# 04_LED.net
KiCad netlist of a schematic drawn in Altium Designer
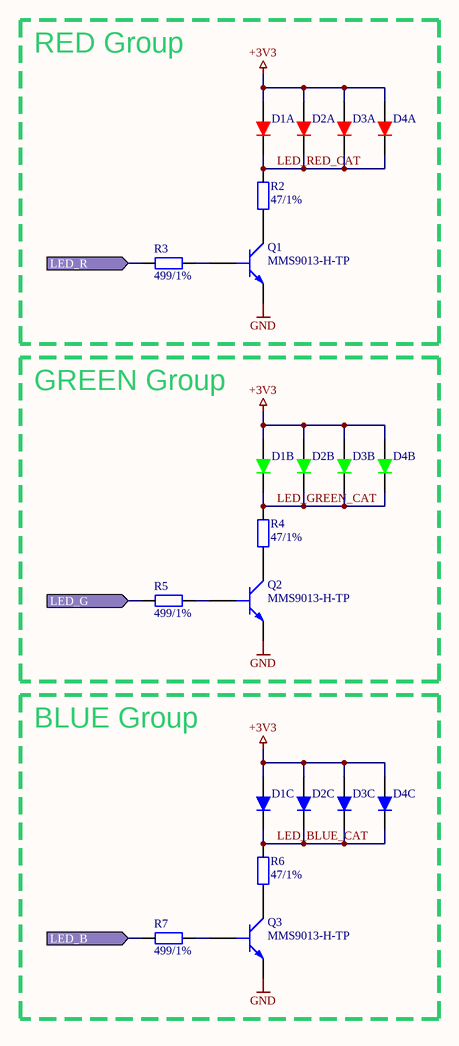
[diagram p0: 04 LED.SchDoc]

(export (version "E")
  (design (tool "Eeschema 10.0.6"))
  (components
    (comp (ref "D1")
      (value "NH-B2020RGBA-HF")
      (footprint "NH-B2020RGBA-HF")
      (description "-30℃~+85℃ Common anode RGB 110° SMD,2.1x2.1mm  Light Emitting Diodes (LED) ROHS")
      (fields (field (name "MANUFACTURER") "Foshan NationStar Optoelectronics"))
      (libsource (lib "altium_symbol") (part "NH-B2020RGBA-HF"))
    )
    (comp (ref "D2")
      (value "NH-B2020RGBA-HF")
      (footprint "NH-B2020RGBA-HF")
      (description "-30℃~+85℃ Common anode RGB 110° SMD,2.1x2.1mm  Light Emitting Diodes (LED) ROHS")
      (fields (field (name "MANUFACTURER") "Foshan NationStar Optoelectronics"))
      (libsource (lib "altium_symbol") (part "NH-B2020RGBA-HF"))
    )
    (comp (ref "D3")
      (value "NH-B2020RGBA-HF")
      (footprint "NH-B2020RGBA-HF")
      (description "-30℃~+85℃ Common anode RGB 110° SMD,2.1x2.1mm  Light Emitting Diodes (LED) ROHS")
      (fields (field (name "MANUFACTURER") "Foshan NationStar Optoelectronics"))
      (libsource (lib "altium_symbol") (part "NH-B2020RGBA-HF"))
    )
    (comp (ref "D4")
      (value "NH-B2020RGBA-HF")
      (footprint "NH-B2020RGBA-HF")
      (description "-30℃~+85℃ Common anode RGB 110° SMD,2.1x2.1mm  Light Emitting Diodes (LED) ROHS")
      (fields (field (name "MANUFACTURER") "Foshan NationStar Optoelectronics"))
      (libsource (lib "altium_symbol") (part "NH-B2020RGBA-HF"))
    )
    (comp (ref "Q1")
      (value "MMS9013-H-TP")
      (footprint "SOT95P237X110-3N")
      (fields (field (name "MANUFACTURER") "MCC(Micro Commercial Components)"))
      (libsource (lib "altium_symbol") (part "MMS9013-H-TP"))
    )
    (comp (ref "Q2")
      (value "MMS9013-H-TP")
      (footprint "SOT95P237X110-3N")
      (fields (field (name "MANUFACTURER") "MCC(Micro Commercial Components)"))
      (libsource (lib "altium_symbol") (part "MMS9013-H-TP"))
    )
    (comp (ref "Q3")
      (value "MMS9013-H-TP")
      (footprint "SOT95P237X110-3N")
      (fields (field (name "MANUFACTURER") "MCC(Micro Commercial Components)"))
      (libsource (lib "altium_symbol") (part "MMS9013-H-TP"))
    )
    (comp (ref "R2")
      (value "47/1%")
      (footprint "RESC1005X04N")
      (description "62.5mW ±5% 47Ω 0402  Chip Resistor - Surface Mount ROHS")
      (fields
        (field (name "MANUFACTURER") "HKR(Hong Kong Resistors)")
        (field (name "MFR_PART_NUMBER") "RCT0247RJLF")
      )
      (libsource (lib "altium_symbol") (part "RCT0247RJLF"))
    )
    (comp (ref "R3")
      (value "499/1%")
      (footprint "RESC1005X04N")
      (fields (field (name "MANUFACTURER") "YAGEO") (field (name "MFR_PART_NUMBER") "RC0402FR-07499RL"))
      (libsource (lib "altium_symbol") (part "RC0402FR-07499RL"))
    )
    (comp (ref "R4")
      (value "47/1%")
      (footprint "RESC1005X04N")
      (description "62.5mW ±5% 47Ω 0402  Chip Resistor - Surface Mount ROHS")
      (fields
        (field (name "MANUFACTURER") "HKR(Hong Kong Resistors)")
        (field (name "MFR_PART_NUMBER") "RCT0247RJLF")
      )
      (libsource (lib "altium_symbol") (part "RCT0247RJLF"))
    )
    (comp (ref "R5")
      (value "499/1%")
      (footprint "RESC1005X04N")
      (fields (field (name "MANUFACTURER") "YAGEO") (field (name "MFR_PART_NUMBER") "RC0402FR-07499RL"))
      (libsource (lib "altium_symbol") (part "RC0402FR-07499RL"))
    )
    (comp (ref "R6")
      (value "47/1%")
      (footprint "RESC1005X04N")
      (description "62.5mW ±5% 47Ω 0402  Chip Resistor - Surface Mount ROHS")
      (fields
        (field (name "MANUFACTURER") "HKR(Hong Kong Resistors)")
        (field (name "MFR_PART_NUMBER") "RCT0247RJLF")
      )
      (libsource (lib "altium_symbol") (part "RCT0247RJLF"))
    )
    (comp (ref "R7")
      (value "499/1%")
      (footprint "RESC1005X04N")
      (fields (field (name "MANUFACTURER") "YAGEO") (field (name "MFR_PART_NUMBER") "RC0402FR-07499RL"))
      (libsource (lib "altium_symbol") (part "RC0402FR-07499RL"))
    )
  )
  (nets
    (net (code "1") (name "+3V3") (class "Default")
      (node (ref "D1") (pin "3") (pinfunction "3_3") (pintype "passive"))
      (node (ref "D2") (pin "3") (pinfunction "3_3") (pintype "passive"))
      (node (ref "D3") (pin "3") (pinfunction "3_3") (pintype "passive"))
      (node (ref "D4") (pin "3") (pinfunction "3_3") (pintype "passive"))
    )
    (net (code "2") (name "/LED_B") (class "Default")
      (node (ref "R7") (pin "2") (pinfunction "2_2") (pintype "passive"))
    )
    (net (code "3") (name "/LED_BLUE_CAT") (class "Default")
      (node (ref "D1") (pin "2") (pinfunction "2_2") (pintype "passive"))
      (node (ref "D2") (pin "2") (pinfunction "2_2") (pintype "passive"))
      (node (ref "D3") (pin "2") (pinfunction "2_2") (pintype "passive"))
      (node (ref "D4") (pin "2") (pinfunction "2_2") (pintype "passive"))
      (node (ref "R6") (pin "2") (pinfunction "2_2") (pintype "passive"))
    )
    (net (code "4") (name "/LED_G") (class "Default")
      (node (ref "R5") (pin "2") (pinfunction "2_2") (pintype "passive"))
    )
    (net (code "5") (name "/LED_GREEN_CAT") (class "Default")
      (node (ref "D1") (pin "4") (pinfunction "4_4") (pintype "passive"))
      (node (ref "D2") (pin "4") (pinfunction "4_4") (pintype "passive"))
      (node (ref "D3") (pin "4") (pinfunction "4_4") (pintype "passive"))
      (node (ref "D4") (pin "4") (pinfunction "4_4") (pintype "passive"))
      (node (ref "R4") (pin "2") (pinfunction "2_2") (pintype "passive"))
    )
    (net (code "6") (name "/LED_R") (class "Default")
      (node (ref "R3") (pin "2") (pinfunction "2_2") (pintype "passive"))
    )
    (net (code "7") (name "/LED_RED_CAT") (class "Default")
      (node (ref "D1") (pin "1") (pinfunction "1_1") (pintype "passive"))
      (node (ref "D2") (pin "1") (pinfunction "1_1") (pintype "passive"))
      (node (ref "D3") (pin "1") (pinfunction "1_1") (pintype "passive"))
      (node (ref "D4") (pin "1") (pinfunction "1_1") (pintype "passive"))
      (node (ref "R2") (pin "2") (pinfunction "2_2") (pintype "passive"))
    )
    (net (code "8") (name "GND") (class "Default")
      (node (ref "Q1") (pin "2") (pinfunction "2_2") (pintype "passive"))
      (node (ref "Q2") (pin "2") (pinfunction "2_2") (pintype "passive"))
      (node (ref "Q3") (pin "2") (pinfunction "2_2") (pintype "passive"))
    )
    (net (code "9") (name "Net-(Q1-Pad1)") (class "Default")
      (node (ref "Q1") (pin "1") (pinfunction "1_1") (pintype "passive"))
      (node (ref "R3") (pin "1") (pinfunction "1_1") (pintype "passive"))
    )
    (net (code "10") (name "Net-(Q1-Pad3)") (class "Default")
      (node (ref "Q1") (pin "3") (pinfunction "3_3") (pintype "passive"))
      (node (ref "R2") (pin "1") (pinfunction "1_1") (pintype "passive"))
    )
    (net (code "11") (name "Net-(Q2-Pad1)") (class "Default")
      (node (ref "Q2") (pin "1") (pinfunction "1_1") (pintype "passive"))
      (node (ref "R5") (pin "1") (pinfunction "1_1") (pintype "passive"))
    )
    (net (code "12") (name "Net-(Q2-Pad3)") (class "Default")
      (node (ref "Q2") (pin "3") (pinfunction "3_3") (pintype "passive"))
      (node (ref "R4") (pin "1") (pinfunction "1_1") (pintype "passive"))
    )
    (net (code "13") (name "Net-(Q3-Pad1)") (class "Default")
      (node (ref "Q3") (pin "1") (pinfunction "1_1") (pintype "passive"))
      (node (ref "R7") (pin "1") (pinfunction "1_1") (pintype "passive"))
    )
    (net (code "14") (name "Net-(Q3-Pad3)") (class "Default")
      (node (ref "Q3") (pin "3") (pinfunction "3_3") (pintype "passive"))
      (node (ref "R6") (pin "1") (pinfunction "1_1") (pintype "passive"))
    )
  )
)
